# Sensor_AirPressure_1Wire.net
KiCad netlist of a schematic drawn in Altium Designer
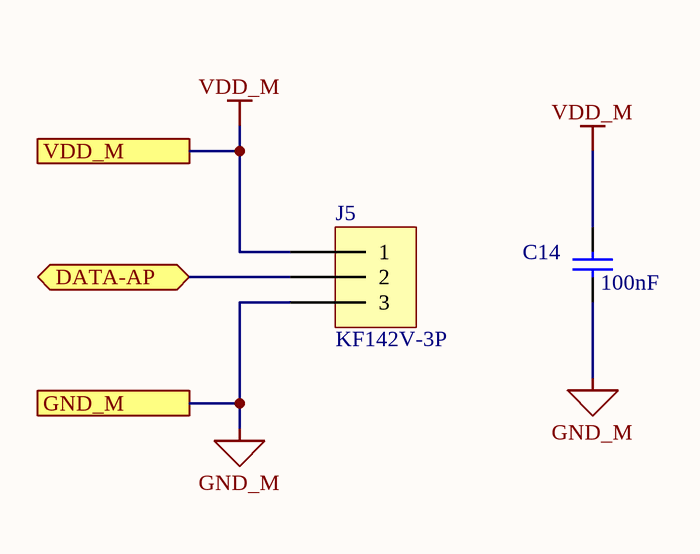
[diagram p0: Sensor_AirPressure_1Wire.SchDoc]

(export (version "E")
  (design (tool "Eeschema 10.0.6"))
  (components
    (comp (ref "C14")
      (value "100nF")
      (footprint "CAPC1608X87N")
      (description "Non-polarised capacitor")
      (fields
        (field (name "PART NUMBER") "CC0603_100NF_50V_10%_X7R")
        (field (name "VOLTAGE") "50V")
        (field (name "AUTHOR") "CERN DEM JLC")
      )
      (libsource (lib "Capacitors") (part "Capacitor - non polarized"))
    )
    (comp (ref "J5")
      (value "KF142V-3P")
      (footprint "CON KF142V-3P-5.08")
      (description "CON KF142V-3P-5.08")
      (libsource (lib "alib_pnphien") (part "CON KF142V-3P-5.08"))
    )
  )
  (nets
    (net (code "1") (name "/DATA-AP") (class "Default")
      (node (ref "J5") (pin "2") (pinfunction "2_2") (pintype "passive"))
    )
    (net (code "2") (name "GND_M") (class "Default")
      (node (ref "C14") (pin "1") (pinfunction "1_1") (pintype "passive"))
      (node (ref "J5") (pin "3") (pinfunction "3_3") (pintype "passive"))
    )
    (net (code "3") (name "VDD_M") (class "Default")
      (node (ref "C14") (pin "2") (pinfunction "2_2") (pintype "passive"))
      (node (ref "J5") (pin "1") (pinfunction "1_1") (pintype "passive"))
    )
  )
)
